# RASPBERRY_CM4.net
KiCad netlist of a schematic drawn in Altium Designer
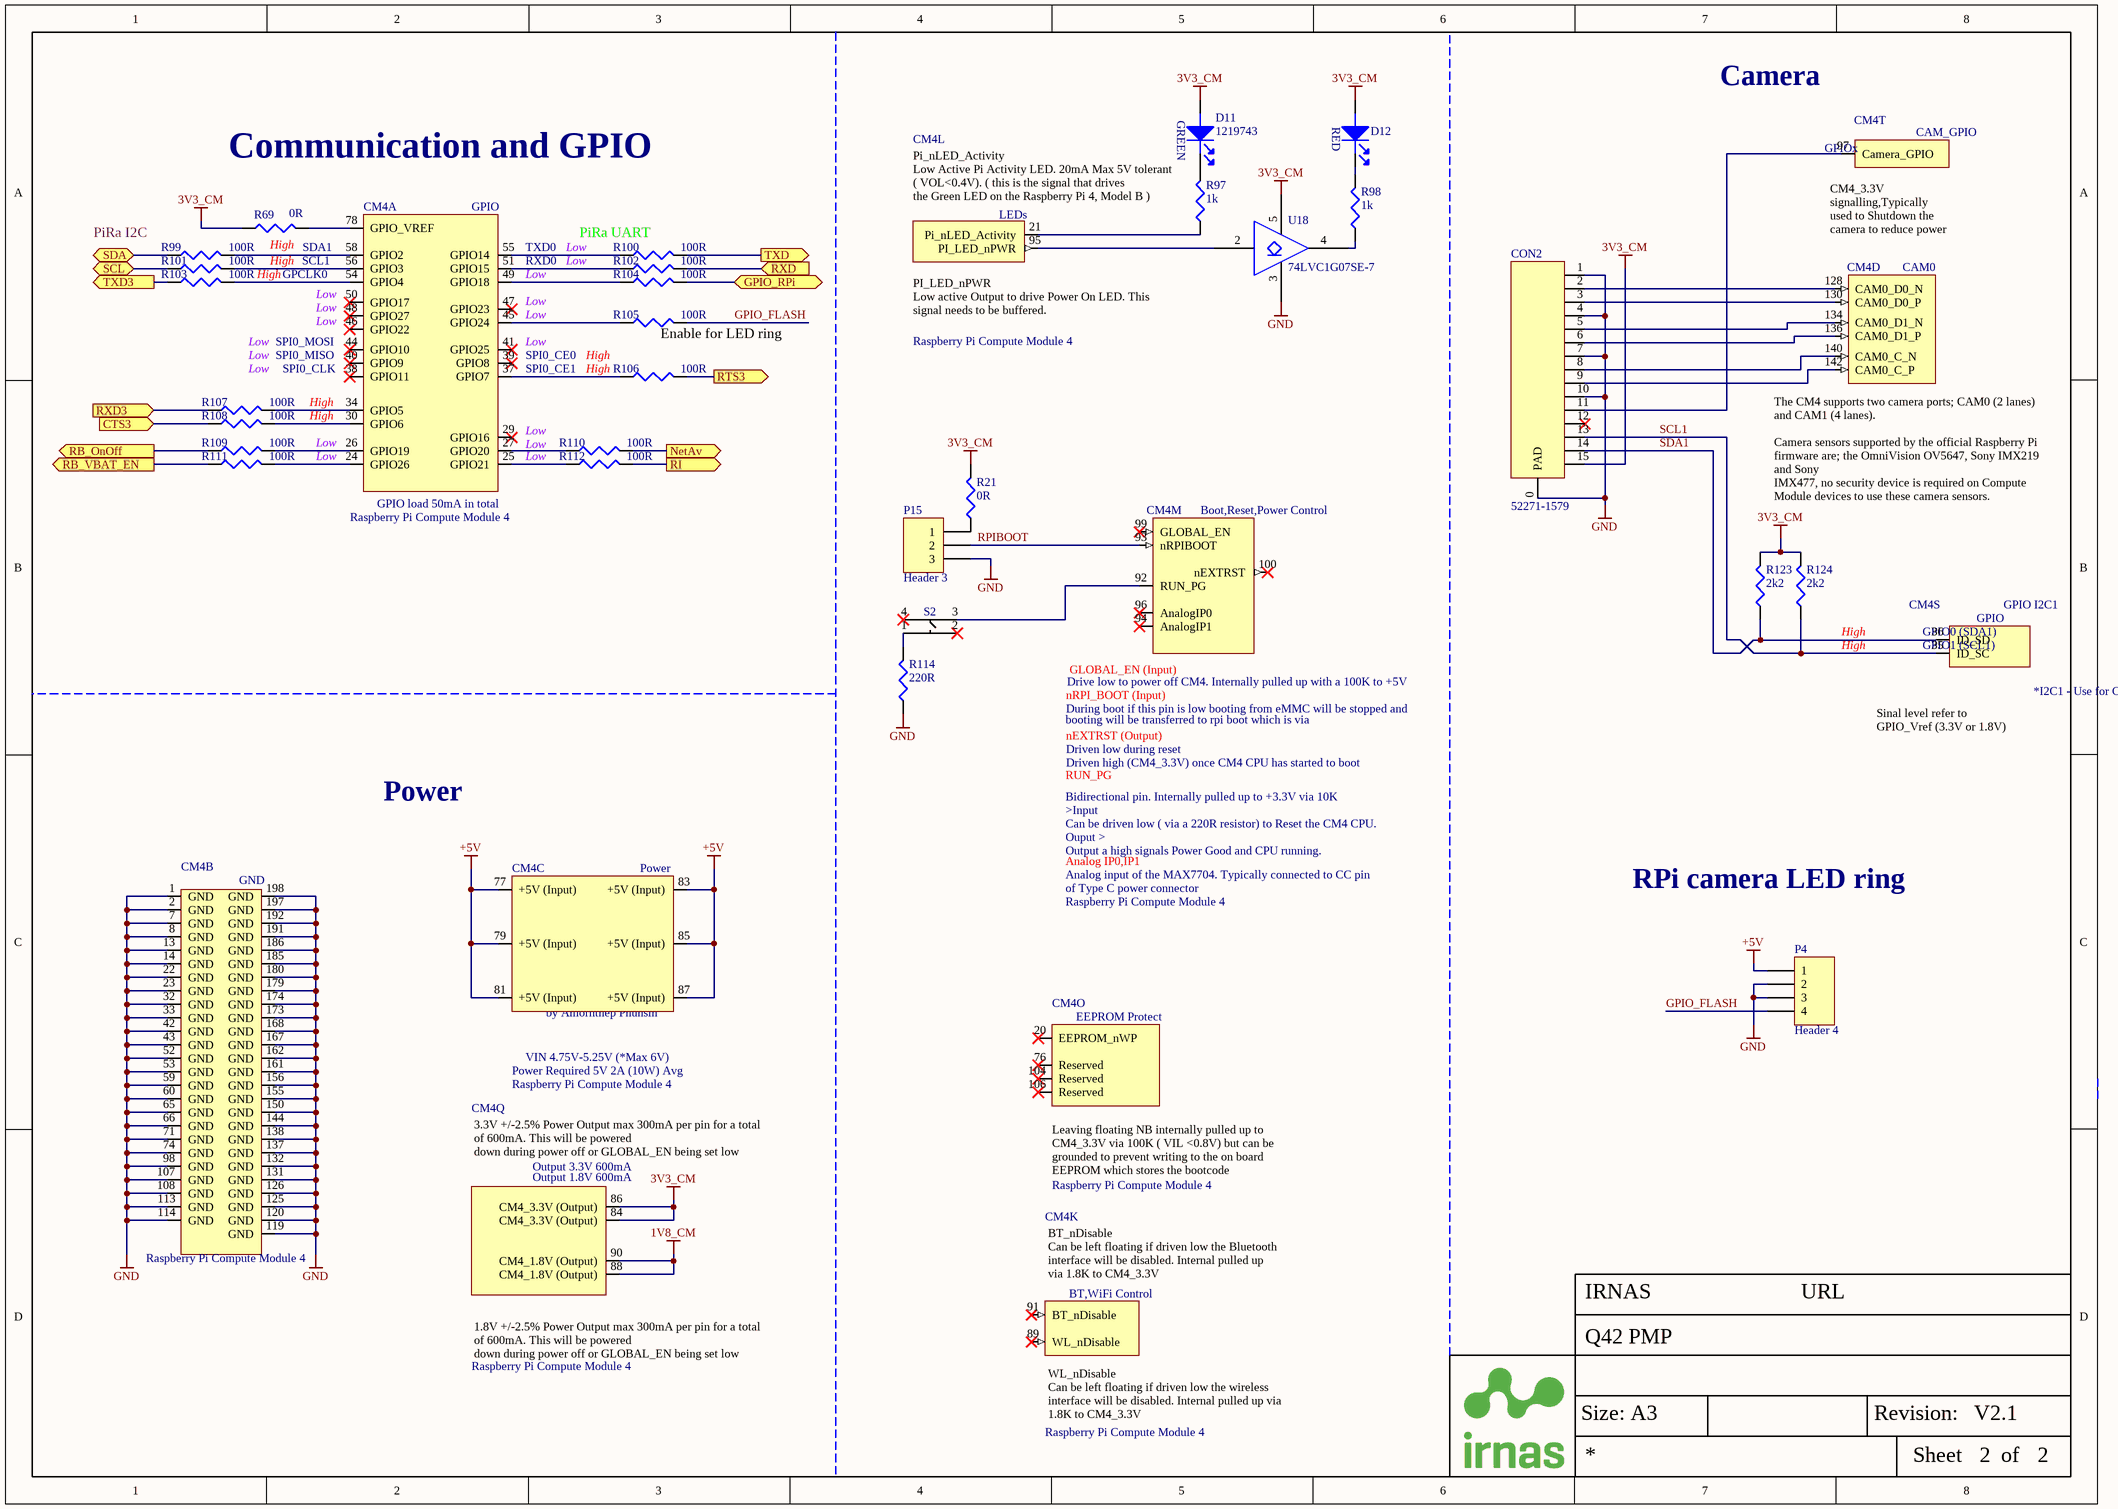
[diagram p0: RASPBERRY CM4.SchDoc]

(export (version "E")
  (design (tool "Eeschema 10.0.6"))
  (components
    (comp (ref "CM4")
      (value "Raspberry Pi Compute Module 4")
      (footprint "Raspberry pi CM4")
      (description "Raspberry Pi Compute Module 4 (! order 2 connectors !)")
      (libsource (lib "Connectors") (part "CM4"))
    )
    (comp (ref "CON2")
      (value "52271-1579")
      (footprint "52271-1579")
      (description "FFC / FPC Board Connector, 1 mm, 15 Contacts, Receptacle, Easy-On 52271 Series, Surface Mount")
      (libsource (lib "Connectors") (part "52271-1579"))
    )
    (comp (ref "D11")
      (value "LED GREEN")
      (footprint "LED0603")
      (description "HSME-C191 -  LED, Green, SMD, 0603, 20 mA, 2.1 V, 572 nm")
      (fields
        (field (name "MANUFACTURER") "BROADCOM LIMITED")
        (field (name "MANUFACTURER PART NUMBER") "HSMS-C190")
        (field (name "SUPPLIER PART NUMBER 1") "1219743")
      )
      (libsource (lib "Active") (part "LED - LED GREEN"))
    )
    (comp (ref "D12")
      (value "LED RED")
      (footprint "LED0603")
      (description "BROADCOM LIMITED - HSMS-C190 - LED, RED, 10MCD, 626NM")
      (fields
        (field (name "MANUFACTURER") "BROADCOM LIMITED")
        (field (name "MANUFACTURER PART NUMBER") "HSMS-C190")
      )
      (libsource (lib "Active") (part "LED - LED RED"))
    )
    (comp (ref "P4")
      (value "Header 4")
      (footprint "HDR1X4")
      (description "Header, 4-Pin")
      (fields (field (name "PUBLISHER") "Altium Limited"))
      (libsource (lib "Miscellaneous Connectors") (part "Header 4"))
    )
    (comp (ref "P15")
      (value "Header 3")
      (footprint "HDR1X3")
      (description "Header, 3-Pin")
      (fields (field (name "PUBLISHER") "Altium Limited"))
      (libsource (lib "Miscellaneous Connectors") (part "Header 3"))
    )
    (comp (ref "R21")
      (value "0R")
      (footprint "RES0603")
      (description "BOURNS - CR0603-J/-000ELF - RES, THICK FILM, 0R, 5%, 0.1W, 0603")
      (fields
        (field (name "MANUFACTURER") "BOURNS")
        (field (name "MANUFACTURER PART NUMBER") "CR0603-J/-000ELF")
      )
      (libsource (lib "Passive") (part "R - 0R"))
    )
    (comp (ref "R69")
      (value "0R")
      (footprint "RES0603")
      (description "BOURNS - CR0603-J/-000ELF - RES, THICK FILM, 0R, 5%, 0.1W, 0603")
      (fields
        (field (name "MANUFACTURER") "BOURNS")
        (field (name "MANUFACTURER PART NUMBER") "CR0603-J/-000ELF")
      )
      (libsource (lib "Passive") (part "R - 0R"))
    )
    (comp (ref "R97")
      (value "1k")
      (footprint "RES0603")
      (description "MULTICOMP - MCMR06X102 JTL - RES, CERAMIC, 1K, 5%, 0.1W, 0603")
      (fields
        (field (name "MANUFACTURER") "MULTICOMP")
        (field (name "MANUFACTURER PART NUMBER") "MCMR06X102 JTL")
      )
      (libsource (lib "Passive") (part "R - 1k"))
    )
    (comp (ref "R98")
      (value "1k")
      (footprint "RES0603")
      (description "MULTICOMP - MCMR06X102 JTL - RES, CERAMIC, 1K, 5%, 0.1W, 0603")
      (fields
        (field (name "MANUFACTURER") "MULTICOMP")
        (field (name "MANUFACTURER PART NUMBER") "MCMR06X102 JTL")
      )
      (libsource (lib "Passive") (part "R - 1k"))
    )
    (comp (ref "R99")
      (value "100R")
      (footprint "RES0603")
      (description "MULTICOMP - MC0063W06031100R - RES, THICK FILM, 100R, 1%, 0.063W, 0603")
      (fields
        (field (name "MANUFACTURER") "MULTICOMP")
        (field (name "MANUFACTURER PART NUMBER") "MC0063W06031100R")
      )
      (libsource (lib "Passive") (part "R - 100R"))
    )
    (comp (ref "R100")
      (value "100R")
      (footprint "RES0603")
      (description "MULTICOMP - MC0063W06031100R - RES, THICK FILM, 100R, 1%, 0.063W, 0603")
      (fields
        (field (name "MANUFACTURER") "MULTICOMP")
        (field (name "MANUFACTURER PART NUMBER") "MC0063W06031100R")
      )
      (libsource (lib "Passive") (part "R - 100R"))
    )
    (comp (ref "R101")
      (value "100R")
      (footprint "RES0603")
      (description "MULTICOMP - MC0063W06031100R - RES, THICK FILM, 100R, 1%, 0.063W, 0603")
      (fields
        (field (name "MANUFACTURER") "MULTICOMP")
        (field (name "MANUFACTURER PART NUMBER") "MC0063W06031100R")
      )
      (libsource (lib "Passive") (part "R - 100R"))
    )
    (comp (ref "R102")
      (value "100R")
      (footprint "RES0603")
      (description "MULTICOMP - MC0063W06031100R - RES, THICK FILM, 100R, 1%, 0.063W, 0603")
      (fields
        (field (name "MANUFACTURER") "MULTICOMP")
        (field (name "MANUFACTURER PART NUMBER") "MC0063W06031100R")
      )
      (libsource (lib "Passive") (part "R - 100R"))
    )
    (comp (ref "R103")
      (value "100R")
      (footprint "RES0603")
      (description "MULTICOMP - MC0063W06031100R - RES, THICK FILM, 100R, 1%, 0.063W, 0603")
      (fields
        (field (name "MANUFACTURER") "MULTICOMP")
        (field (name "MANUFACTURER PART NUMBER") "MC0063W06031100R")
      )
      (libsource (lib "Passive") (part "R - 100R"))
    )
    (comp (ref "R104")
      (value "100R")
      (footprint "RES0603")
      (description "MULTICOMP - MC0063W06031100R - RES, THICK FILM, 100R, 1%, 0.063W, 0603")
      (fields
        (field (name "MANUFACTURER") "MULTICOMP")
        (field (name "MANUFACTURER PART NUMBER") "MC0063W06031100R")
      )
      (libsource (lib "Passive") (part "R - 100R"))
    )
    (comp (ref "R105")
      (value "100R")
      (footprint "RES0603")
      (description "MULTICOMP - MC0063W06031100R - RES, THICK FILM, 100R, 1%, 0.063W, 0603")
      (fields
        (field (name "MANUFACTURER") "MULTICOMP")
        (field (name "MANUFACTURER PART NUMBER") "MC0063W06031100R")
      )
      (libsource (lib "Passive") (part "R - 100R"))
    )
    (comp (ref "R106")
      (value "100R")
      (footprint "RES0603")
      (description "MULTICOMP - MC0063W06031100R - RES, THICK FILM, 100R, 1%, 0.063W, 0603")
      (fields
        (field (name "MANUFACTURER") "MULTICOMP")
        (field (name "MANUFACTURER PART NUMBER") "MC0063W06031100R")
      )
      (libsource (lib "Passive") (part "R - 100R"))
    )
    (comp (ref "R107")
      (value "100R")
      (footprint "RES0603")
      (description "MULTICOMP - MC0063W06031100R - RES, THICK FILM, 100R, 1%, 0.063W, 0603")
      (fields
        (field (name "MANUFACTURER") "MULTICOMP")
        (field (name "MANUFACTURER PART NUMBER") "MC0063W06031100R")
      )
      (libsource (lib "Passive") (part "R - 100R"))
    )
    (comp (ref "R108")
      (value "100R")
      (footprint "RES0603")
      (description "MULTICOMP - MC0063W06031100R - RES, THICK FILM, 100R, 1%, 0.063W, 0603")
      (fields
        (field (name "MANUFACTURER") "MULTICOMP")
        (field (name "MANUFACTURER PART NUMBER") "MC0063W06031100R")
      )
      (libsource (lib "Passive") (part "R - 100R"))
    )
    (comp (ref "R109")
      (value "100R")
      (footprint "RES0603")
      (description "MULTICOMP - MC0063W06031100R - RES, THICK FILM, 100R, 1%, 0.063W, 0603")
      (fields
        (field (name "MANUFACTURER") "MULTICOMP")
        (field (name "MANUFACTURER PART NUMBER") "MC0063W06031100R")
      )
      (libsource (lib "Passive") (part "R - 100R"))
    )
    (comp (ref "R110")
      (value "100R")
      (footprint "RES0603")
      (description "MULTICOMP - MC0063W06031100R - RES, THICK FILM, 100R, 1%, 0.063W, 0603")
      (fields
        (field (name "MANUFACTURER") "MULTICOMP")
        (field (name "MANUFACTURER PART NUMBER") "MC0063W06031100R")
      )
      (libsource (lib "Passive") (part "R - 100R"))
    )
    (comp (ref "R111")
      (value "100R")
      (footprint "RES0603")
      (description "MULTICOMP - MC0063W06031100R - RES, THICK FILM, 100R, 1%, 0.063W, 0603")
      (fields
        (field (name "MANUFACTURER") "MULTICOMP")
        (field (name "MANUFACTURER PART NUMBER") "MC0063W06031100R")
      )
      (libsource (lib "Passive") (part "R - 100R"))
    )
    (comp (ref "R112")
      (value "100R")
      (footprint "RES0603")
      (description "MULTICOMP - MC0063W06031100R - RES, THICK FILM, 100R, 1%, 0.063W, 0603")
      (fields
        (field (name "MANUFACTURER") "MULTICOMP")
        (field (name "MANUFACTURER PART NUMBER") "MC0063W06031100R")
      )
      (libsource (lib "Passive") (part "R - 100R"))
    )
    (comp (ref "R114")
      (value "220R")
      (footprint "RES0603")
      (description "MULTICOMP - MCWR06X2200FTL - RES, THICK FILM, 220R, 1%, 0.1W, 0603")
      (fields
        (field (name "MANUFACTURER") "MULTICOMP")
        (field (name "MANUFACTURER PART NUMBER") "MCWR06X2200FTL")
      )
      (libsource (lib "Passive") (part "R - 220R"))
    )
    (comp (ref "R123")
      (value "2k2")
      (footprint "RES0603")
      (description "MULTICOMP - MCMR06X2201FTL - RES, CERAMIC, 2K2, 1%, 0.1W, 0603")
      (fields
        (field (name "MANUFACTURER") "MULTICOMP")
        (field (name "MANUFACTURER PART NUMBER") "MCMR06X2201FTL")
      )
      (libsource (lib "Passive") (part "R - 2k2"))
    )
    (comp (ref "R124")
      (value "2k2")
      (footprint "RES0603")
      (description "MULTICOMP - MCMR06X2201FTL - RES, CERAMIC, 2K2, 1%, 0.1W, 0603")
      (fields
        (field (name "MANUFACTURER") "MULTICOMP")
        (field (name "MANUFACTURER PART NUMBER") "MCMR06X2201FTL")
      )
      (libsource (lib "Passive") (part "R - 2k2"))
    )
    (comp (ref "S2")
      (value "BTN - KMR221NGLFS")
      (footprint "SW")
      (description "SWITCH TACTILE SPST-NO 0.05A 32V")
      (fields (field (name "MANUFACTURER") "ITT C&K") (field (name "MANUFACTURER PART NUMBER") "KMR221NGLFS"))
      (libsource (lib "Mechanical") (part "BTN - KMR221NGLFS"))
    )
    (comp (ref "U18")
      (value "74LVC1G07SE-7")
      (footprint "SOT-353")
      (description "Buffer, 74LVC1G07, 1.65 V to 5.5 V, SOT-353-5")
      (libsource (lib "Active") (part "D - 74LVC1G07SE-7"))
    )
  )
  (nets
    (net (code "1") (name "+5V") (class "Default")
      (node (ref "CM4") (pin "77") (pinfunction "+5V_(Input)_77") (pintype "power_in"))
      (node (ref "CM4") (pin "79") (pinfunction "+5V_(Input)_79") (pintype "power_in"))
      (node (ref "CM4") (pin "81") (pinfunction "+5V_(Input)_81") (pintype "power_in"))
      (node (ref "CM4") (pin "83") (pinfunction "+5V_(Input)_83") (pintype "power_in"))
      (node (ref "CM4") (pin "85") (pinfunction "+5V_(Input)_85") (pintype "power_in"))
      (node (ref "CM4") (pin "87") (pinfunction "+5V_(Input)_87") (pintype "power_in"))
      (node (ref "P4") (pin "1") (pinfunction "1_1") (pintype "passive"))
    )
    (net (code "2") (name "/CTS3") (class "Default")
      (node (ref "R108") (pin "1") (pinfunction "1_1") (pintype "passive"))
    )
    (net (code "3") (name "/GPIO_FLASH") (class "Default")
      (node (ref "P4") (pin "4") (pinfunction "4_4") (pintype "passive"))
      (node (ref "R105") (pin "2") (pinfunction "2_2") (pintype "passive"))
    )
    (net (code "4") (name "/GPIO_RPi") (class "Default")
      (node (ref "R104") (pin "2") (pinfunction "2_2") (pintype "passive"))
    )
    (net (code "5") (name "/NetAv") (class "Default")
      (node (ref "R110") (pin "2") (pinfunction "2_2") (pintype "passive"))
    )
    (net (code "6") (name "/RB_OnOff") (class "Default")
      (node (ref "R109") (pin "1") (pinfunction "1_1") (pintype "passive"))
    )
    (net (code "7") (name "/RB_VBAT_EN") (class "Default")
      (node (ref "R111") (pin "1") (pinfunction "1_1") (pintype "passive"))
    )
    (net (code "8") (name "/RI") (class "Default")
      (node (ref "R112") (pin "2") (pinfunction "2_2") (pintype "passive"))
    )
    (net (code "9") (name "/RPIBOOT") (class "Default")
      (node (ref "CM4") (pin "93") (pinfunction "nRPIBOOT_93") (pintype "input"))
      (node (ref "P15") (pin "2") (pinfunction "2_2") (pintype "passive"))
    )
    (net (code "10") (name "/RTS3") (class "Default")
      (node (ref "R106") (pin "2") (pinfunction "2_2") (pintype "passive"))
    )
    (net (code "11") (name "/RXD") (class "Default")
      (node (ref "R102") (pin "2") (pinfunction "2_2") (pintype "passive"))
    )
    (net (code "12") (name "/RXD3") (class "Default")
      (node (ref "R107") (pin "1") (pinfunction "1_1") (pintype "passive"))
    )
    (net (code "13") (name "/SCL") (class "Default")
      (node (ref "R101") (pin "1") (pinfunction "1_1") (pintype "passive"))
    )
    (net (code "14") (name "/SCL1") (class "Default")
      (node (ref "CM4") (pin "35") (pinfunction "ID_SC_35") (pintype "passive"))
      (node (ref "CON2") (pin "13") (pinfunction "13_13") (pintype "passive"))
      (node (ref "R124") (pin "1") (pinfunction "1_1") (pintype "passive"))
    )
    (net (code "15") (name "/SDA") (class "Default")
      (node (ref "R99") (pin "1") (pinfunction "1_1") (pintype "passive"))
    )
    (net (code "16") (name "/SDA1") (class "Default")
      (node (ref "CM4") (pin "36") (pinfunction "ID_SD_36") (pintype "passive"))
      (node (ref "CON2") (pin "14") (pinfunction "14_14") (pintype "passive"))
      (node (ref "R123") (pin "1") (pinfunction "1_1") (pintype "passive"))
    )
    (net (code "17") (name "/TXD") (class "Default")
      (node (ref "R100") (pin "2") (pinfunction "2_2") (pintype "passive"))
    )
    (net (code "18") (name "/TXD3") (class "Default")
      (node (ref "R103") (pin "1") (pinfunction "1_1") (pintype "passive"))
    )
    (net (code "19") (name "1V8_CM") (class "Default")
      (node (ref "CM4") (pin "88") (pinfunction "CM4_1.8V_(Output)_88") (pintype "power_in"))
      (node (ref "CM4") (pin "90") (pinfunction "CM4_1.8V_(Output)_90") (pintype "power_in"))
    )
    (net (code "20") (name "3V3_CM") (class "Default")
      (node (ref "CM4") (pin "84") (pinfunction "CM4_3.3V_(Output)_84") (pintype "power_in"))
      (node (ref "CM4") (pin "86") (pinfunction "CM4_3.3V_(Output)_86") (pintype "power_in"))
      (node (ref "CON2") (pin "15") (pinfunction "15_15") (pintype "passive"))
      (node (ref "D11") (pin "2") (pinfunction "ANODE_2") (pintype "passive"))
      (node (ref "D12") (pin "2") (pinfunction "ANODE_2") (pintype "passive"))
      (node (ref "R123") (pin "2") (pinfunction "2_2") (pintype "passive"))
      (node (ref "R124") (pin "2") (pinfunction "2_2") (pintype "passive"))
      (node (ref "R21") (pin "2") (pinfunction "2_2") (pintype "passive"))
      (node (ref "R69") (pin "1") (pinfunction "1_1") (pintype "passive"))
      (node (ref "U18") (pin "5") (pinfunction "VCC_5") (pintype "passive"))
    )
    (net (code "21") (name "GND") (class "Default")
      (node (ref "CM4") (pin "1") (pinfunction "GND_1") (pintype "power_in"))
      (node (ref "CM4") (pin "107") (pinfunction "GND_107") (pintype "power_in"))
      (node (ref "CM4") (pin "108") (pinfunction "GND_108") (pintype "power_in"))
      (node (ref "CM4") (pin "113") (pinfunction "GND_113") (pintype "power_in"))
      (node (ref "CM4") (pin "114") (pinfunction "GND_114") (pintype "power_in"))
      (node (ref "CM4") (pin "119") (pinfunction "GND_119") (pintype "power_in"))
      (node (ref "CM4") (pin "120") (pinfunction "GND_120") (pintype "power_in"))
      (node (ref "CM4") (pin "125") (pinfunction "GND_125") (pintype "power_in"))
      (node (ref "CM4") (pin "126") (pinfunction "GND_126") (pintype "power_in"))
      (node (ref "CM4") (pin "13") (pinfunction "GND_13") (pintype "power_in"))
      (node (ref "CM4") (pin "131") (pinfunction "GND_131") (pintype "power_in"))
      (node (ref "CM4") (pin "132") (pinfunction "GND_132") (pintype "power_in"))
      (node (ref "CM4") (pin "137") (pinfunction "GND_137") (pintype "power_in"))
      (node (ref "CM4") (pin "138") (pinfunction "GND_138") (pintype "power_in"))
      (node (ref "CM4") (pin "14") (pinfunction "GND_14") (pintype "power_in"))
      (node (ref "CM4") (pin "144") (pinfunction "GND_144") (pintype "power_in"))
      (node (ref "CM4") (pin "150") (pinfunction "GND_150") (pintype "power_in"))
      (node (ref "CM4") (pin "155") (pinfunction "GND_155") (pintype "power_in"))
      (node (ref "CM4") (pin "156") (pinfunction "GND_156") (pintype "power_in"))
      (node (ref "CM4") (pin "161") (pinfunction "GND_161") (pintype "power_in"))
      (node (ref "CM4") (pin "162") (pinfunction "GND_162") (pintype "power_in"))
      (node (ref "CM4") (pin "167") (pinfunction "GND_167") (pintype "power_in"))
      (node (ref "CM4") (pin "168") (pinfunction "GND_168") (pintype "power_in"))
      (node (ref "CM4") (pin "173") (pinfunction "GND_173") (pintype "power_in"))
      (node (ref "CM4") (pin "174") (pinfunction "GND_174") (pintype "power_in"))
      (node (ref "CM4") (pin "179") (pinfunction "GND_179") (pintype "power_in"))
      (node (ref "CM4") (pin "180") (pinfunction "GND_180") (pintype "power_in"))
      (node (ref "CM4") (pin "185") (pinfunction "GND_185") (pintype "power_in"))
      (node (ref "CM4") (pin "186") (pinfunction "GND_186") (pintype "power_in"))
      (node (ref "CM4") (pin "191") (pinfunction "GND_191") (pintype "power_in"))
      (node (ref "CM4") (pin "192") (pinfunction "GND_192") (pintype "power_in"))
      (node (ref "CM4") (pin "197") (pinfunction "GND_197") (pintype "power_in"))
      (node (ref "CM4") (pin "198") (pinfunction "GND_198") (pintype "power_in"))
      (node (ref "CM4") (pin "2") (pinfunction "GND_2") (pintype "power_in"))
      (node (ref "CM4") (pin "22") (pinfunction "GND_22") (pintype "power_in"))
      (node (ref "CM4") (pin "23") (pinfunction "GND_23") (pintype "power_in"))
      (node (ref "CM4") (pin "32") (pinfunction "GND_32") (pintype "power_in"))
      (node (ref "CM4") (pin "33") (pinfunction "GND_33") (pintype "power_in"))
      (node (ref "CM4") (pin "42") (pinfunction "GND_42") (pintype "power_in"))
      (node (ref "CM4") (pin "43") (pinfunction "GND_43") (pintype "power_in"))
      (node (ref "CM4") (pin "52") (pinfunction "GND_52") (pintype "power_in"))
      (node (ref "CM4") (pin "53") (pinfunction "GND_53") (pintype "power_in"))
      (node (ref "CM4") (pin "59") (pinfunction "GND_59") (pintype "power_in"))
      (node (ref "CM4") (pin "60") (pinfunction "GND_60") (pintype "power_in"))
      (node (ref "CM4") (pin "65") (pinfunction "GND_65") (pintype "power_in"))
      (node (ref "CM4") (pin "66") (pinfunction "GND_66") (pintype "power_in"))
      (node (ref "CM4") (pin "7") (pinfunction "GND_7") (pintype "power_in"))
      (node (ref "CM4") (pin "71") (pinfunction "GND_71") (pintype "power_in"))
      (node (ref "CM4") (pin "74") (pinfunction "GND_74") (pintype "power_in"))
      (node (ref "CM4") (pin "8") (pinfunction "GND_8") (pintype "power_in"))
      (node (ref "CM4") (pin "98") (pinfunction "GND_98") (pintype "power_in"))
      (node (ref "CON2") (pin "0") (pinfunction "PAD_0") (pintype "passive"))
      (node (ref "CON2") (pin "1") (pinfunction "1_1") (pintype "passive"))
      (node (ref "CON2") (pin "10") (pinfunction "10_10") (pintype "passive"))
      (node (ref "CON2") (pin "4") (pinfunction "4_4") (pintype "passive"))
      (node (ref "CON2") (pin "7") (pinfunction "7_7") (pintype "passive"))
      (node (ref "P15") (pin "3") (pinfunction "3_3") (pintype "passive"))
      (node (ref "P4") (pin "2") (pinfunction "2_2") (pintype "passive"))
      (node (ref "P4") (pin "3") (pinfunction "3_3") (pintype "passive"))
      (node (ref "R114") (pin "1") (pinfunction "1_1") (pintype "passive"))
      (node (ref "U18") (pin "3") (pinfunction "GND_3") (pintype "passive"))
    )
    (net (code "22") (name "Net-(CM4A-GPIO2)") (class "Default")
      (node (ref "CM4") (pin "58") (pinfunction "GPIO2_58") (pintype "passive"))
      (node (ref "R99") (pin "2") (pinfunction "2_2") (pintype "passive"))
    )
    (net (code "23") (name "Net-(CM4A-GPIO3)") (class "Default")
      (node (ref "CM4") (pin "56") (pinfunction "GPIO3_56") (pintype "passive"))
      (node (ref "R101") (pin "2") (pinfunction "2_2") (pintype "passive"))
    )
    (net (code "24") (name "Net-(CM4A-GPIO4)") (class "Default")
      (node (ref "CM4") (pin "54") (pinfunction "GPIO4_54") (pintype "passive"))
      (node (ref "R103") (pin "2") (pinfunction "2_2") (pintype "passive"))
    )
    (net (code "25") (name "Net-(CM4A-GPIO5)") (class "Default")
      (node (ref "CM4") (pin "34") (pinfunction "GPIO5_34") (pintype "passive"))
      (node (ref "R107") (pin "2") (pinfunction "2_2") (pintype "passive"))
    )
    (net (code "26") (name "Net-(CM4A-GPIO6)") (class "Default")
      (node (ref "CM4") (pin "30") (pinfunction "GPIO6_30") (pintype "passive"))
      (node (ref "R108") (pin "2") (pinfunction "2_2") (pintype "passive"))
    )
    (net (code "27") (name "Net-(CM4A-GPIO7)") (class "Default")
      (node (ref "CM4") (pin "37") (pinfunction "GPIO7_37") (pintype "passive"))
      (node (ref "R106") (pin "1") (pinfunction "1_1") (pintype "passive"))
    )
    (net (code "28") (name "Net-(CM4A-GPIO14)") (class "Default")
      (node (ref "CM4") (pin "55") (pinfunction "GPIO14_55") (pintype "passive"))
      (node (ref "R100") (pin "1") (pinfunction "1_1") (pintype "passive"))
    )
    (net (code "29") (name "Net-(CM4A-GPIO15)") (class "Default")
      (node (ref "CM4") (pin "51") (pinfunction "GPIO15_51") (pintype "passive"))
      (node (ref "R102") (pin "1") (pinfunction "1_1") (pintype "passive"))
    )
    (net (code "30") (name "Net-(CM4A-GPIO18)") (class "Default")
      (node (ref "CM4") (pin "49") (pinfunction "GPIO18_49") (pintype "passive"))
      (node (ref "R104") (pin "1") (pinfunction "1_1") (pintype "passive"))
    )
    (net (code "31") (name "Net-(CM4A-GPIO19)") (class "Default")
      (node (ref "CM4") (pin "26") (pinfunction "GPIO19_26") (pintype "passive"))
      (node (ref "R109") (pin "2") (pinfunction "2_2") (pintype "passive"))
    )
    (net (code "32") (name "Net-(CM4A-GPIO20)") (class "Default")
      (node (ref "CM4") (pin "27") (pinfunction "GPIO20_27") (pintype "passive"))
      (node (ref "R110") (pin "1") (pinfunction "1_1") (pintype "passive"))
    )
    (net (code "33") (name "Net-(CM4A-GPIO21)") (class "Default")
      (node (ref "CM4") (pin "25") (pinfunction "GPIO21_25") (pintype "passive"))
      (node (ref "R112") (pin "1") (pinfunction "1_1") (pintype "passive"))
    )
    (net (code "34") (name "Net-(CM4A-GPIO24)") (class "Default")
      (node (ref "CM4") (pin "45") (pinfunction "GPIO24_45") (pintype "passive"))
      (node (ref "R105") (pin "1") (pinfunction "1_1") (pintype "passive"))
    )
    (net (code "35") (name "Net-(CM4A-GPIO26)") (class "Default")
      (node (ref "CM4") (pin "24") (pinfunction "GPIO26_24") (pintype "passive"))
      (node (ref "R111") (pin "2") (pinfunction "2_2") (pintype "passive"))
    )
    (net (code "36") (name "Net-(CM4A-GPIO_VREF)") (class "Default")
      (node (ref "CM4") (pin "78") (pinfunction "GPIO_VREF_78") (pintype "power_in"))
      (node (ref "R69") (pin "2") (pinfunction "2_2") (pintype "passive"))
    )
    (net (code "37") (name "Net-(CM4D-CAM0_C_N)") (class "Default")
      (node (ref "CM4") (pin "140") (pinfunction "CAM0_C_N_140") (pintype "input"))
      (node (ref "CON2") (pin "8") (pinfunction "8_8") (pintype "passive"))
    )
    (net (code "38") (name "Net-(CM4D-CAM0_C_P)") (class "Default")
      (node (ref "CM4") (pin "142") (pinfunction "CAM0_C_P_142") (pintype "input"))
      (node (ref "CON2") (pin "9") (pinfunction "9_9") (pintype "passive"))
    )
    (net (code "39") (name "Net-(CM4D-CAM0_D0_N)") (class "Default")
      (node (ref "CM4") (pin "128") (pinfunction "CAM0_D0_N_128") (pintype "input"))
      (node (ref "CON2") (pin "2") (pinfunction "2_2") (pintype "passive"))
    )
    (net (code "40") (name "Net-(CM4D-CAM0_D0_P)") (class "Default")
      (node (ref "CM4") (pin "130") (pinfunction "CAM0_D0_P_130") (pintype "input"))
      (node (ref "CON2") (pin "3") (pinfunction "3_3") (pintype "passive"))
    )
    (net (code "41") (name "Net-(CM4D-CAM0_D1_N)") (class "Default")
      (node (ref "CM4") (pin "134") (pinfunction "CAM0_D1_N_134") (pintype "input"))
      (node (ref "CON2") (pin "5") (pinfunction "5_5") (pintype "passive"))
    )
    (net (code "42") (name "Net-(CM4D-CAM0_D1_P)") (class "Default")
      (node (ref "CM4") (pin "136") (pinfunction "CAM0_D1_P_136") (pintype "input"))
      (node (ref "CON2") (pin "6") (pinfunction "6_6") (pintype "passive"))
    )
    (net (code "43") (name "Net-(CM4L-PI_LED_nPWR)") (class "Default")
      (node (ref "CM4") (pin "95") (pinfunction "PI_LED_nPWR_95") (pintype "output"))
      (node (ref "U18") (pin "2") (pinfunction "2_2") (pintype "passive"))
    )
    (net (code "44") (name "Net-(CM4L-Pi_nLED_Activity)") (class "Default")
      (node (ref "CM4") (pin "21") (pinfunction "Pi_nLED_Activity_21") (pintype "open_collector"))
      (node (ref "R97") (pin "1") (pinfunction "1_1") (pintype "passive"))
    )
    (net (code "45") (name "Net-(CM4M-RUN_PG)") (class "Default")
      (node (ref "CM4") (pin "92") (pinfunction "RUN_PG_92") (pintype "passive"))
      (node (ref "S2") (pin "3") (pinfunction "3_3") (pintype "passive"))
    )
    (net (code "46") (name "Net-(CM4T-Camera_GPIO)") (class "Default")
      (node (ref "CM4") (pin "97") (pinfunction "Camera_GPIO_97") (pintype "passive"))
      (node (ref "CON2") (pin "11") (pinfunction "11_11") (pintype "passive"))
    )
    (net (code "47") (name "Net-(D11-cathode)") (class "Default")
      (node (ref "D11") (pin "1") (pinfunction "cathode_1") (pintype "passive"))
      (node (ref "R97") (pin "2") (pinfunction "2_2") (pintype "passive"))
    )
    (net (code "48") (name "Net-(D12-cathode)") (class "Default")
      (node (ref "D12") (pin "1") (pinfunction "cathode_1") (pintype "passive"))
      (node (ref "R98") (pin "2") (pinfunction "2_2") (pintype "passive"))
    )
    (net (code "49") (name "Net-(P15-Pad1)") (class "Default")
      (node (ref "P15") (pin "1") (pinfunction "1_1") (pintype "passive"))
      (node (ref "R21") (pin "1") (pinfunction "1_1") (pintype "passive"))
    )
    (net (code "50") (name "Net-(R98-Pad1)") (class "Default")
      (node (ref "R98") (pin "1") (pinfunction "1_1") (pintype "passive"))
      (node (ref "U18") (pin "4") (pinfunction "4_4") (pintype "passive"))
    )
    (net (code "51") (name "Net-(R114-Pad2)") (class "Default")
      (node (ref "R114") (pin "2") (pinfunction "2_2") (pintype "passive"))
      (node (ref "S2") (pin "1") (pinfunction "1_1") (pintype "passive"))
    )
    (net (code "52") (name "unconnected-(CM4A-GPIO8-Pad39)") (class "Default")
      (node (ref "CM4") (pin "39") (pinfunction "GPIO8_39") (pintype "passive+no_connect"))
    )
    (net (code "53") (name "unconnected-(CM4A-GPIO9-Pad40)") (class "Default")
      (node (ref "CM4") (pin "40") (pinfunction "GPIO9_40") (pintype "passive+no_connect"))
    )
    (net (code "54") (name "unconnected-(CM4A-GPIO10-Pad44)") (class "Default")
      (node (ref "CM4") (pin "44") (pinfunction "GPIO10_44") (pintype "passive+no_connect"))
    )
    (net (code "55") (name "unconnected-(CM4A-GPIO11-Pad38)") (class "Default")
      (node (ref "CM4") (pin "38") (pinfunction "GPIO11_38") (pintype "passive+no_connect"))
    )
    (net (code "56") (name "unconnected-(CM4A-GPIO16-Pad29)") (class "Default")
      (node (ref "CM4") (pin "29") (pinfunction "GPIO16_29") (pintype "passive+no_connect"))
    )
    (net (code "57") (name "unconnected-(CM4A-GPIO17-Pad50)") (class "Default")
      (node (ref "CM4") (pin "50") (pinfunction "GPIO17_50") (pintype "passive+no_connect"))
    )
    (net (code "58") (name "unconnected-(CM4A-GPIO22-Pad46)") (class "Default")
      (node (ref "CM4") (pin "46") (pinfunction "GPIO22_46") (pintype "passive+no_connect"))
    )
    (net (code "59") (name "unconnected-(CM4A-GPIO23-Pad47)") (class "Default")
      (node (ref "CM4") (pin "47") (pinfunction "GPIO23_47") (pintype "passive+no_connect"))
    )
    (net (code "60") (name "unconnected-(CM4A-GPIO25-Pad41)") (class "Default")
      (node (ref "CM4") (pin "41") (pinfunction "GPIO25_41") (pintype "passive+no_connect"))
    )
    (net (code "61") (name "unconnected-(CM4A-GPIO27-Pad48)") (class "Default")
      (node (ref "CM4") (pin "48") (pinfunction "GPIO27_48") (pintype "passive+no_connect"))
    )
    (net (code "62") (name "unconnected-(CM4K-BT_nDisable-Pad91)") (class "Default")
      (node (ref "CM4") (pin "91") (pinfunction "BT_nDisable_91") (pintype "input+no_connect"))
    )
    (net (code "63") (name "unconnected-(CM4K-WL_nDisable-Pad89)") (class "Default")
      (node (ref "CM4") (pin "89") (pinfunction "WL_nDisable_89") (pintype "input+no_connect"))
    )
    (net (code "64") (name "unconnected-(CM4M-AnalogIP0-Pad96)") (class "Default")
      (node (ref "CM4") (pin "96") (pinfunction "AnalogIP0_96") (pintype "passive+no_connect"))
    )
    (net (code "65") (name "unconnected-(CM4M-AnalogIP1-Pad94)") (class "Default")
      (node (ref "CM4") (pin "94") (pinfunction "AnalogIP1_94") (pintype "passive+no_connect"))
    )
    (net (code "66") (name "unconnected-(CM4M-GLOBAL_EN-Pad99)") (class "Default")
      (node (ref "CM4") (pin "99") (pinfunction "GLOBAL_EN_99") (pintype "input+no_connect"))
    )
    (net (code "67") (name "unconnected-(CM4M-nEXTRST-Pad100)") (class "Default")
      (node (ref "CM4") (pin "100") (pinfunction "nEXTRST_100") (pintype "output+no_connect"))
    )
    (net (code "68") (name "unconnected-(CM4O-EEPROM_nWP-Pad20)") (class "Default")
      (node (ref "CM4") (pin "20") (pinfunction "EEPROM_nWP_20") (pintype "passive+no_connect"))
    )
    (net (code "69") (name "unconnected-(CM4O-Reserved-Pad76)") (class "Default")
      (node (ref "CM4") (pin "76") (pinfunction "Reserved_76") (pintype "passive+no_connect"))
    )
    (net (code "70") (name "unconnected-(CM4O-Reserved-Pad104)") (class "Default")
      (node (ref "CM4") (pin "104") (pinfunction "Reserved_104") (pintype "passive+no_connect"))
    )
    (net (code "71") (name "unconnected-(CM4O-Reserved-Pad106)") (class "Default")
      (node (ref "CM4") (pin "106") (pinfunction "Reserved_106") (pintype "passive+no_connect"))
    )
    (net (code "72") (name "unconnected-(CON2-Pad12)") (class "Default")
      (node (ref "CON2") (pin "12") (pinfunction "12_12") (pintype "passive+no_connect"))
    )
    (net (code "73") (name "unconnected-(S2-Pad2)") (class "Default")
      (node (ref "S2") (pin "2") (pinfunction "2_2") (pintype "passive+no_connect"))
    )
    (net (code "74") (name "unconnected-(S2-Pad4)") (class "Default")
      (node (ref "S2") (pin "4") (pinfunction "4_4") (pintype "passive+no_connect"))
    )
  )
)
